# EEPROM.net
KiCad netlist of a schematic drawn in EAGLE
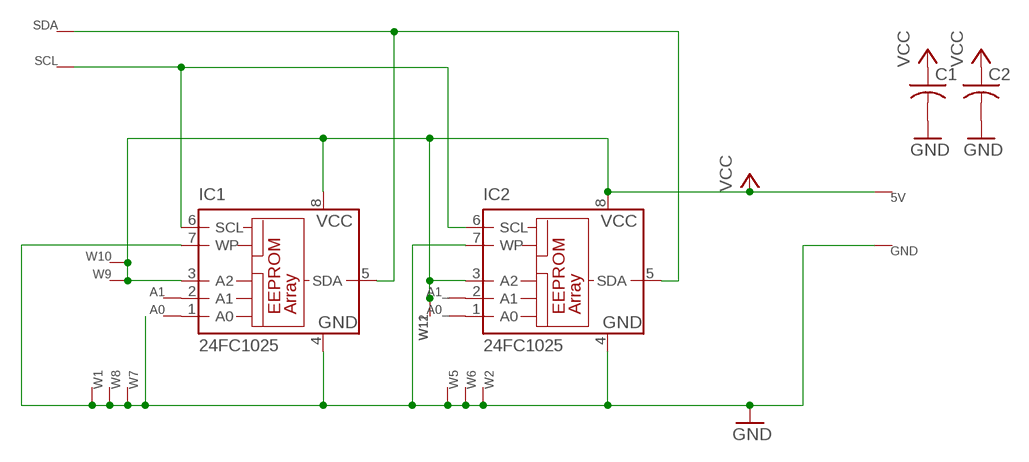
[diagram p0: schematic, sheet 1]

(export (version "E")
  (design (tool "Eeschema 10.0.6"))
  (components
    (comp (ref "5V")
      (value "WIRE-VIA8")
      (footprint "eagle-import:VIA8")
      (libsource (lib "eagle-import") (part "WIRE-VIA8"))
    )
    (comp (ref "A0")
      (value "WIRE-VIA8")
      (footprint "eagle-import:VIA8")
      (libsource (lib "eagle-import") (part "WIRE-VIA8"))
    )
    (comp (ref "A0_")
      (value "WIRE-VIA8")
      (footprint "eagle-import:VIA8")
      (libsource (lib "eagle-import") (part "WIRE-VIA8"))
    )
    (comp (ref "A1")
      (value "WIRE-VIA8")
      (footprint "eagle-import:VIA8")
      (libsource (lib "eagle-import") (part "WIRE-VIA8"))
    )
    (comp (ref "A1_")
      (value "WIRE-VIA8")
      (footprint "eagle-import:VIA8")
      (libsource (lib "eagle-import") (part "WIRE-VIA8"))
    )
    (comp (ref "C1")
      (value "C-US-5MM")
      (footprint "eagle-import:C050-024X044")
      (libsource (lib "eagle-import") (part "C-US-5MM"))
    )
    (comp (ref "C2")
      (value "C-US-5MM")
      (footprint "eagle-import:C050-024X044")
      (libsource (lib "eagle-import") (part "C-US-5MM"))
    )
    (comp (ref "GND")
      (value "WIRE-VIA8")
      (footprint "eagle-import:VIA8")
      (libsource (lib "eagle-import") (part "WIRE-VIA8"))
    )
    (comp (ref "IC1")
      (value "24FC1025")
      (footprint "eagle-import:DIL8")
      (fields (field (name "MF") "MICROCHIP") (field (name "MPN") "24LC128-I/P"))
      (libsource (lib "eagle-import") (part "24PLC128"))
    )
    (comp (ref "IC2")
      (value "24FC1025")
      (footprint "eagle-import:DIL8")
      (fields (field (name "MF") "MICROCHIP") (field (name "MPN") "24LC128-I/P"))
      (libsource (lib "eagle-import") (part "24PLC128"))
    )
    (comp (ref "SCL")
      (value "WIRE-VIA8")
      (footprint "eagle-import:VIA8")
      (libsource (lib "eagle-import") (part "WIRE-VIA8"))
    )
    (comp (ref "SDA")
      (value "WIRE-VIA8")
      (footprint "eagle-import:VIA8")
      (libsource (lib "eagle-import") (part "WIRE-VIA8"))
    )
    (comp (ref "W1")
      (value "WIRE-VIA8")
      (footprint "eagle-import:VIA8")
      (libsource (lib "eagle-import") (part "WIRE-VIA8"))
    )
    (comp (ref "W2")
      (value "WIRE-VIA8")
      (footprint "eagle-import:VIA8")
      (libsource (lib "eagle-import") (part "WIRE-VIA8"))
    )
    (comp (ref "W5")
      (value "WIRE-VIA8")
      (footprint "eagle-import:VIA8")
      (libsource (lib "eagle-import") (part "WIRE-VIA8"))
    )
    (comp (ref "W6")
      (value "WIRE-VIA8")
      (footprint "eagle-import:VIA8")
      (libsource (lib "eagle-import") (part "WIRE-VIA8"))
    )
    (comp (ref "W7")
      (value "WIRE-VIA8")
      (footprint "eagle-import:VIA8")
      (libsource (lib "eagle-import") (part "WIRE-VIA8"))
    )
    (comp (ref "W8")
      (value "WIRE-VIA8")
      (footprint "eagle-import:VIA8")
      (libsource (lib "eagle-import") (part "WIRE-VIA8"))
    )
    (comp (ref "W9")
      (value "WIRE-VIA8")
      (footprint "eagle-import:VIA8")
      (libsource (lib "eagle-import") (part "WIRE-VIA8"))
    )
    (comp (ref "W10")
      (value "WIRE-VIA8")
      (footprint "eagle-import:VIA8")
      (libsource (lib "eagle-import") (part "WIRE-VIA8"))
    )
    (comp (ref "W11")
      (value "WIRE-VIA8")
      (footprint "eagle-import:VIA8")
      (libsource (lib "eagle-import") (part "WIRE-VIA8"))
    )
    (comp (ref "W12")
      (value "WIRE-VIA8")
      (footprint "eagle-import:VIA8")
      (libsource (lib "eagle-import") (part "WIRE-VIA8"))
    )
  )
  (nets
    (net (code "1") (name "GND") (class "Default")
      (node (ref "C1") (pin "2") (pinfunction "2_2") (pintype "passive"))
      (node (ref "C2") (pin "2") (pinfunction "2_2") (pintype "passive"))
      (node (ref "GND") (pin "P$1") (pinfunction "P$1_P$1") (pintype "bidirectional"))
      (node (ref "IC1") (pin "4") (pinfunction "GND_4") (pintype "power_in"))
      (node (ref "IC1") (pin "7") (pinfunction "WP_7") (pintype "input"))
      (node (ref "IC2") (pin "4") (pinfunction "GND_4") (pintype "power_in"))
      (node (ref "IC2") (pin "7") (pinfunction "WP_7") (pintype "input"))
      (node (ref "W1") (pin "P$1") (pinfunction "P$1_P$1") (pintype "bidirectional"))
      (node (ref "W2") (pin "P$1") (pinfunction "P$1_P$1") (pintype "bidirectional"))
      (node (ref "W5") (pin "P$1") (pinfunction "P$1_P$1") (pintype "bidirectional"))
      (node (ref "W6") (pin "P$1") (pinfunction "P$1_P$1") (pintype "bidirectional"))
      (node (ref "W7") (pin "P$1") (pinfunction "P$1_P$1") (pintype "bidirectional"))
      (node (ref "W8") (pin "P$1") (pinfunction "P$1_P$1") (pintype "bidirectional"))
    )
    (net (code "2") (name "Net-(IC1-A0)") (class "Default")
      (node (ref "A0") (pin "P$1") (pinfunction "P$1_P$1") (pintype "bidirectional"))
      (node (ref "IC1") (pin "1") (pinfunction "A0_1") (pintype "input"))
    )
    (net (code "3") (name "Net-(IC1-A1)") (class "Default")
      (node (ref "A1") (pin "P$1") (pinfunction "P$1_P$1") (pintype "bidirectional"))
      (node (ref "IC1") (pin "2") (pinfunction "A1_2") (pintype "input"))
    )
    (net (code "4") (name "Net-(IC1-SCL)") (class "Default")
      (node (ref "IC1") (pin "6") (pinfunction "SCL_6") (pintype "input"))
      (node (ref "IC2") (pin "6") (pinfunction "SCL_6") (pintype "input"))
      (node (ref "SCL") (pin "P$1") (pinfunction "P$1_P$1") (pintype "bidirectional"))
    )
    (net (code "5") (name "Net-(IC1-SDA)") (class "Default")
      (node (ref "IC1") (pin "5") (pinfunction "SDA_5") (pintype "bidirectional"))
      (node (ref "IC2") (pin "5") (pinfunction "SDA_5") (pintype "bidirectional"))
      (node (ref "SDA") (pin "P$1") (pinfunction "P$1_P$1") (pintype "bidirectional"))
    )
    (net (code "6") (name "Net-(IC2-A0)") (class "Default")
      (node (ref "A0_") (pin "P$1") (pinfunction "P$1_P$1") (pintype "bidirectional"))
      (node (ref "IC2") (pin "1") (pinfunction "A0_1") (pintype "input"))
    )
    (net (code "7") (name "Net-(IC2-A1)") (class "Default")
      (node (ref "A1_") (pin "P$1") (pinfunction "P$1_P$1") (pintype "bidirectional"))
      (node (ref "IC2") (pin "2") (pinfunction "A1_2") (pintype "input"))
    )
    (net (code "8") (name "VCC") (class "Default")
      (node (ref "5V") (pin "P$1") (pinfunction "P$1_P$1") (pintype "bidirectional"))
      (node (ref "C1") (pin "1") (pinfunction "1_1") (pintype "passive"))
      (node (ref "C2") (pin "1") (pinfunction "1_1") (pintype "passive"))
      (node (ref "IC1") (pin "3") (pinfunction "A2_3") (pintype "input"))
      (node (ref "IC1") (pin "8") (pinfunction "VCC_8") (pintype "power_in"))
      (node (ref "IC2") (pin "3") (pinfunction "A2_3") (pintype "input"))
      (node (ref "IC2") (pin "8") (pinfunction "VCC_8") (pintype "power_in"))
      (node (ref "W10") (pin "P$1") (pinfunction "P$1_P$1") (pintype "bidirectional"))
      (node (ref "W11") (pin "P$1") (pinfunction "P$1_P$1") (pintype "bidirectional"))
      (node (ref "W12") (pin "P$1") (pinfunction "P$1_P$1") (pintype "bidirectional"))
      (node (ref "W9") (pin "P$1") (pinfunction "P$1_P$1") (pintype "bidirectional"))
    )
  )
)
